# Sch1.net
KiCad netlist of a schematic drawn in Altium Designer
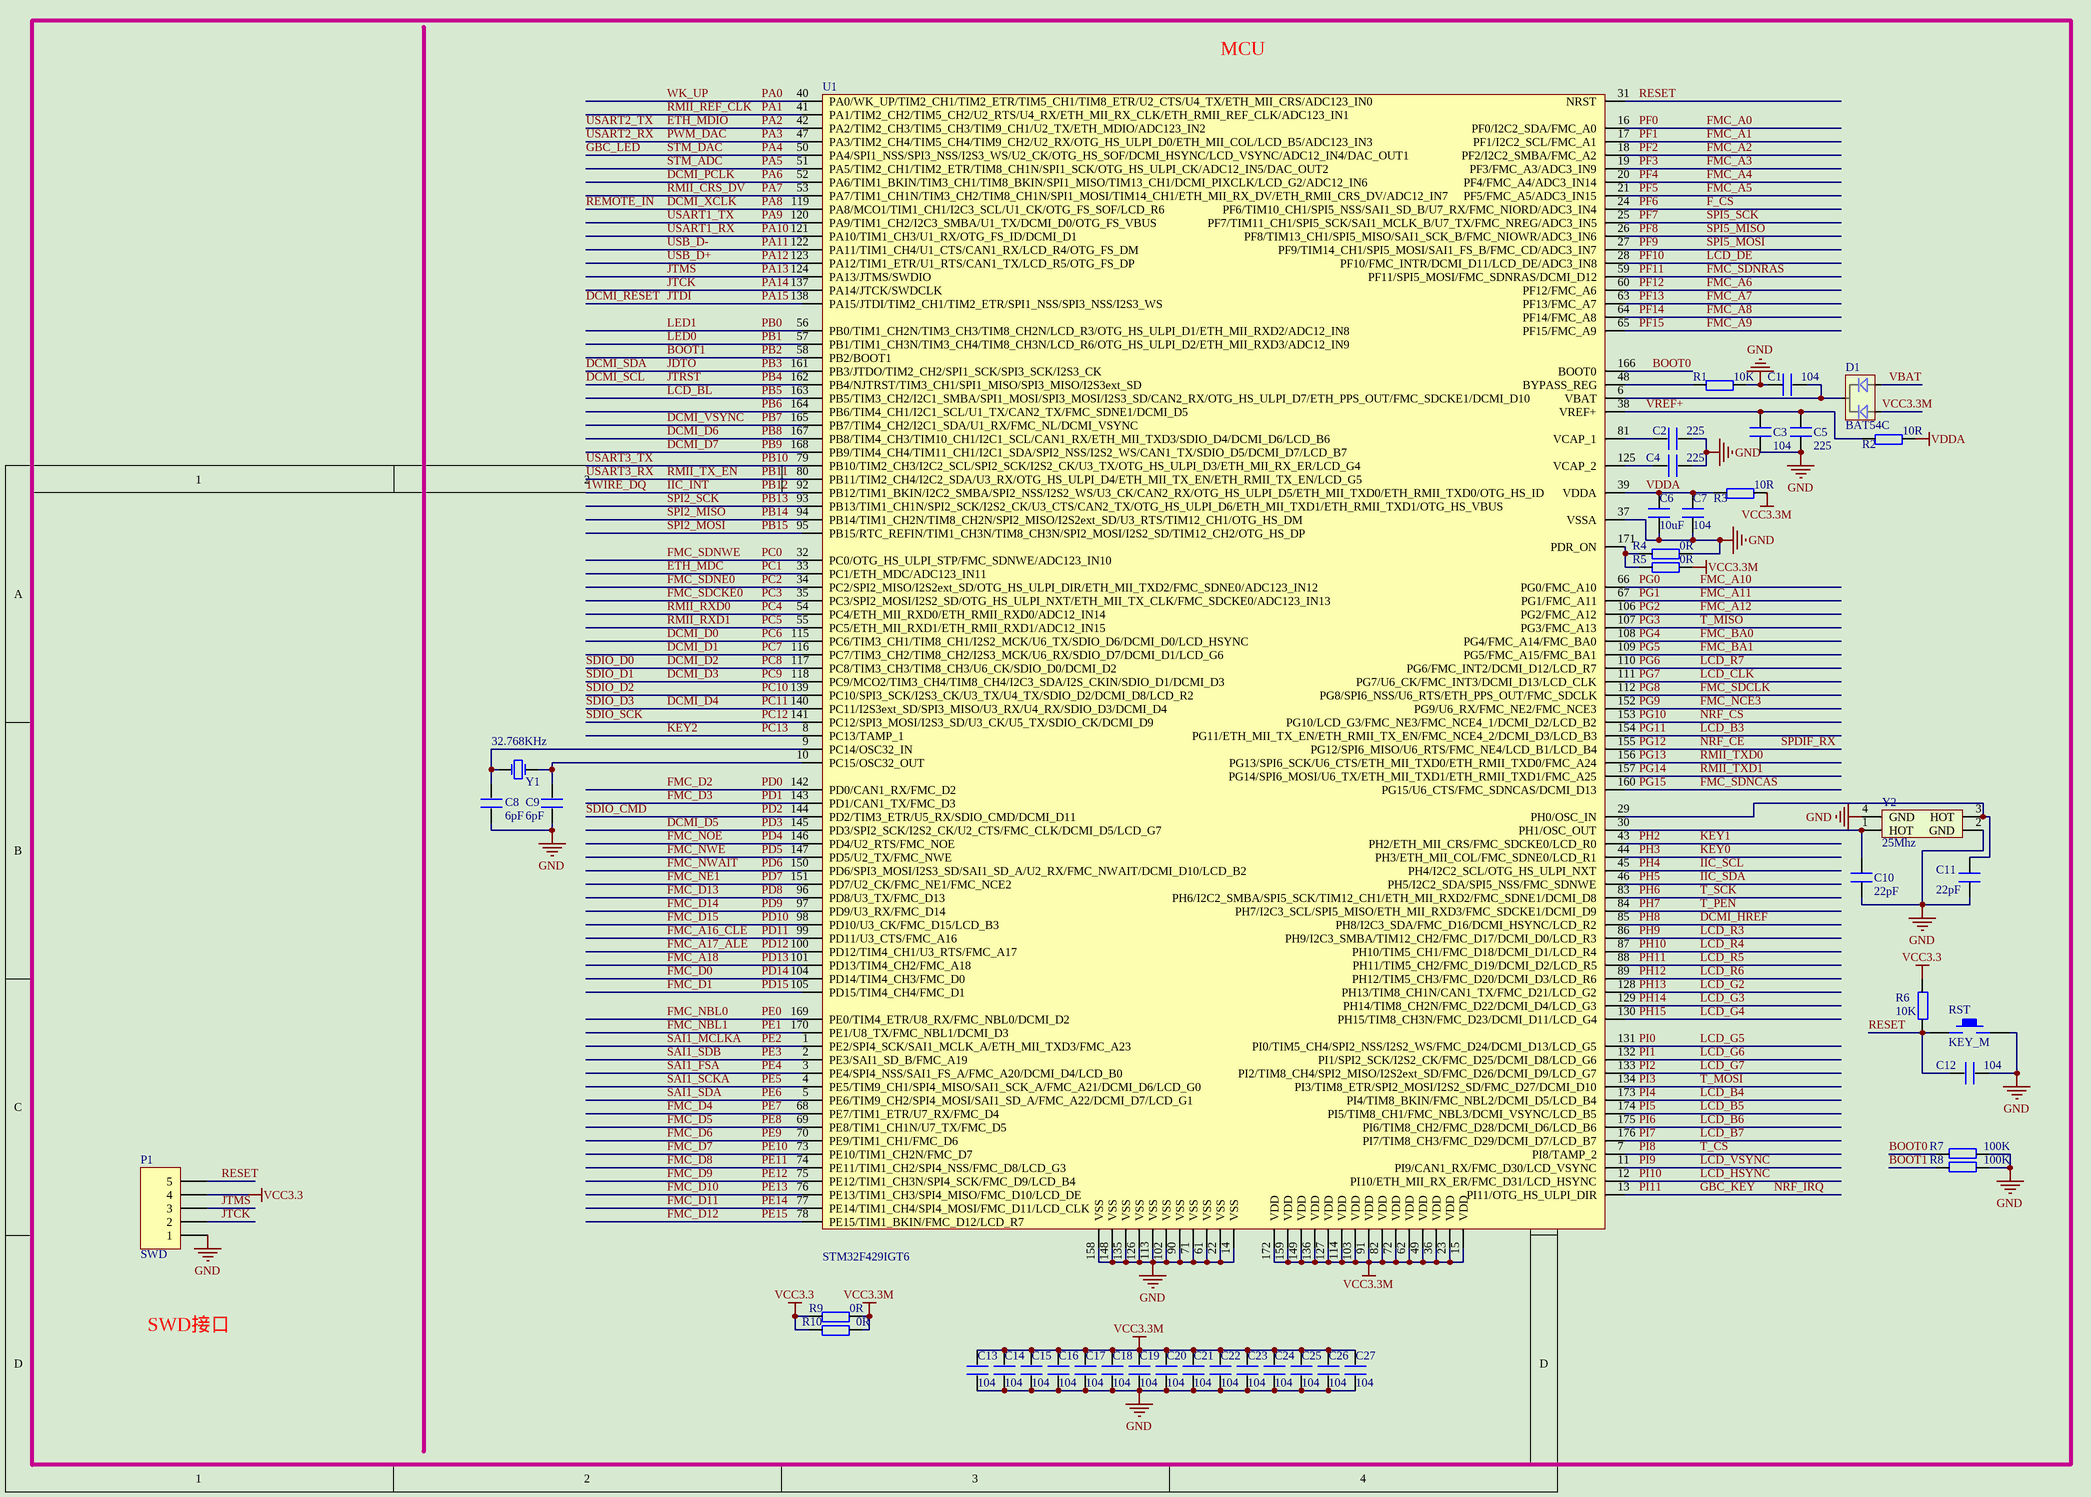
[diagram p0: Sch1.SchDoc]

(export (version "E")
  (design (tool "Eeschema 10.0.6"))
  (components
    (comp (ref "C1") (value "104") (footprint "0402") (libsource (lib "STM32F429_CORE") (part "C")))
    (comp (ref "C2") (value "225") (footprint "0402") (libsource (lib "STM32F429_CORE") (part "C")))
    (comp (ref "C3") (value "104") (footprint "0402") (libsource (lib "STM32F429_CORE") (part "C")))
    (comp (ref "C4") (value "225") (footprint "0402") (libsource (lib "STM32F429_CORE") (part "C")))
    (comp (ref "C5") (value "225") (footprint "0402") (libsource (lib "STM32F429_CORE") (part "C")))
    (comp (ref "C6") (value "10uF") (footprint "0603P") (libsource (lib "STM32F429_CORE") (part "C")))
    (comp (ref "C7") (value "104") (footprint "0402") (libsource (lib "STM32F429_CORE") (part "C")))
    (comp (ref "C8") (value "6pF") (footprint "0402") (libsource (lib "STM32F429_CORE") (part "C")))
    (comp (ref "C9") (value "6pF") (footprint "0402") (libsource (lib "STM32F429_CORE") (part "C")))
    (comp (ref "C10") (value "22pF") (footprint "0402") (libsource (lib "STM32F429_CORE") (part "C")))
    (comp (ref "C11") (value "22pF") (footprint "0402") (libsource (lib "STM32F429_CORE") (part "C")))
    (comp (ref "C12") (value "104") (footprint "0402") (libsource (lib "STM32F429_CORE") (part "C")))
    (comp (ref "C13") (value "104") (footprint "0402") (libsource (lib "STM32F429_CORE") (part "C")))
    (comp (ref "C14") (value "104") (footprint "0402") (libsource (lib "STM32F429_CORE") (part "C")))
    (comp (ref "C15") (value "104") (footprint "0402") (libsource (lib "STM32F429_CORE") (part "C")))
    (comp (ref "C16") (value "104") (footprint "0402") (libsource (lib "STM32F429_CORE") (part "C")))
    (comp (ref "C17") (value "104") (footprint "0402") (libsource (lib "STM32F429_CORE") (part "C")))
    (comp (ref "C18") (value "104") (footprint "0402") (libsource (lib "STM32F429_CORE") (part "C")))
    (comp (ref "C19") (value "104") (footprint "0402") (libsource (lib "STM32F429_CORE") (part "C")))
    (comp (ref "C20") (value "104") (footprint "0402") (libsource (lib "STM32F429_CORE") (part "C")))
    (comp (ref "C21") (value "104") (footprint "0402") (libsource (lib "STM32F429_CORE") (part "C")))
    (comp (ref "C22") (value "104") (footprint "0402") (libsource (lib "STM32F429_CORE") (part "C")))
    (comp (ref "C23") (value "104") (footprint "0402") (libsource (lib "STM32F429_CORE") (part "C")))
    (comp (ref "C24") (value "104") (footprint "0402") (libsource (lib "STM32F429_CORE") (part "C")))
    (comp (ref "C25") (value "104") (footprint "0402") (libsource (lib "STM32F429_CORE") (part "C")))
    (comp (ref "C26") (value "104") (footprint "0402") (libsource (lib "STM32F429_CORE") (part "C")))
    (comp (ref "C27") (value "104") (footprint "0402") (libsource (lib "STM32F429_CORE") (part "C")))
    (comp (ref "D1")
      (value "BAT54C")
      (footprint "SOT-23")
      (description "双肖特基二极管")
      (libsource (lib "STM32F429_CORE") (part "BAT54C"))
    )
    (comp (ref "P1")
      (value "SWD")
      (footprint "HDR1X5")
      (description "Header, 5-Pin")
      (fields (field (name "PUBLISHER") "Altium Limited"))
      (libsource (lib "STM32F429_CORE") (part "Header 5"))
    )
    (comp (ref "R1") (value "10K") (footprint "0402") (libsource (lib "STM32F429_CORE") (part "R")))
    (comp (ref "R2") (value "10R") (footprint "0402") (libsource (lib "STM32F429_CORE") (part "R")))
    (comp (ref "R3") (value "10R") (footprint "0402") (libsource (lib "STM32F429_CORE") (part "R")))
    (comp (ref "R4") (value "0R") (footprint "0402") (libsource (lib "STM32F429_CORE") (part "R")))
    (comp (ref "R5") (value "0R") (footprint "0402") (libsource (lib "STM32F429_CORE") (part "R")))
    (comp (ref "R6") (value "10K") (footprint "0402") (libsource (lib "STM32F429_CORE") (part "R")))
    (comp (ref "R7") (value "100K") (footprint "0402") (libsource (lib "STM32F429_CORE") (part "R")))
    (comp (ref "R8") (value "100K") (footprint "0402") (libsource (lib "STM32F429_CORE") (part "R")))
    (comp (ref "R9") (value "0R") (footprint "0402") (libsource (lib "STM32F429_CORE") (part "R")))
    (comp (ref "R10") (value "0R") (footprint "0402") (libsource (lib "STM32F429_CORE") (part "R")))
    (comp (ref "RST")
      (value "KEY_M")
      (footprint "KEY_SOP3625")
      (libsource (lib "STM32F429_CORE") (part "KEY_M"))
    )
    (comp (ref "U1")
      (value "STM32F429IGT6")
      (footprint "LQFP176")
      (libsource (lib "STM32F429_CORE") (part "STM32F429IGT6"))
    )
    (comp (ref "Y1")
      (value "32.768KHz")
      (footprint "XTAL3215")
      (description "普通晶振")
      (fields (field (name "PUBLISHER") "Altium Limited"))
      (libsource (lib "STM32F429_CORE") (part "XTAL"))
    )
    (comp (ref "Y2")
      (value "25Mhz")
      (footprint "XTAL3225")
      (description "3225贴片无源晶振")
      (libsource (lib "STM32F429_CORE") (part "XTAL_3225"))
    )
  )
  (nets
    (net (code "1") (name "/1WIRE_DQ") (class "Default")
      (node (ref "U1") (pin "92") (pinfunction "PB12/TIM1_BKIN/I2C2_SMBA/SPI2_NSS/I2S2_WS/U3_CK/CAN2_RX/OTG_HS_ULPI_D5/ETH_MII_TXD0/ETH_RMII_TXD0/OTG_HS_ID_92") (pintype "passive"))
    )
    (net (code "2") (name "/BOOT0") (class "Default")
      (node (ref "R7") (pin "2") (pintype "passive"))
      (node (ref "U1") (pin "166") (pinfunction "BOOT0_166") (pintype "passive"))
    )
    (net (code "3") (name "/BOOT1") (class "Default")
      (node (ref "R8") (pin "2") (pintype "passive"))
      (node (ref "U1") (pin "58") (pinfunction "PB2/BOOT1_58") (pintype "passive"))
    )
    (net (code "4") (name "/DCMI_D0") (class "Default")
      (node (ref "U1") (pin "115") (pinfunction "PC6/TIM3_CH1/TIM8_CH1/I2S2_MCK/U6_TX/SDIO_D6/DCMI_D0/LCD_HSYNC_115") (pintype "passive"))
    )
    (net (code "5") (name "/DCMI_D1") (class "Default")
      (node (ref "U1") (pin "116") (pinfunction "PC7/TIM3_CH2/TIM8_CH2/I2S3_MCK/U6_RX/SDIO_D7/DCMI_D1/LCD_G6_116") (pintype "passive"))
    )
    (net (code "6") (name "/DCMI_D2") (class "Default")
      (node (ref "U1") (pin "117") (pinfunction "PC8/TIM3_CH3/TIM8_CH3/U6_CK/SDIO_D0/DCMI_D2_117") (pintype "passive"))
    )
    (net (code "7") (name "/DCMI_D3") (class "Default")
      (node (ref "U1") (pin "118") (pinfunction "PC9/MCO2/TIM3_CH4/TIM8_CH4/I2C3_SDA/I2S_CKIN/SDIO_D1/DCMI_D3_118") (pintype "passive"))
    )
    (net (code "8") (name "/DCMI_D4") (class "Default")
      (node (ref "U1") (pin "140") (pinfunction "PC11/I2S3ext_SD/SPI3_MISO/U3_RX/U4_RX/SDIO_D3/DCMI_D4_140") (pintype "passive"))
    )
    (net (code "9") (name "/DCMI_D5") (class "Default")
      (node (ref "U1") (pin "145") (pinfunction "PD3/SPI2_SCK/I2S2_CK/U2_CTS/FMC_CLK/DCMI_D5/LCD_G7_145") (pintype "passive"))
    )
    (net (code "10") (name "/DCMI_D6") (class "Default")
      (node (ref "U1") (pin "167") (pinfunction "PB8/TIM4_CH3/TIM10_CH1/I2C1_SCL/CAN1_RX/ETH_MII_TXD3/SDIO_D4/DCMI_D6/LCD_B6_167") (pintype "passive"))
    )
    (net (code "11") (name "/DCMI_D7") (class "Default")
      (node (ref "U1") (pin "168") (pinfunction "PB9/TIM4_CH4/TIM11_CH1/I2C1_SDA/SPI2_NSS/I2S2_WS/CAN1_TX/SDIO_D5/DCMI_D7/LCD_B7_168") (pintype "passive"))
    )
    (net (code "12") (name "/DCMI_HREF") (class "Default")
      (node (ref "U1") (pin "85") (pinfunction "PH8/I2C3_SDA/FMC_D16/DCMI_HSYNC/LCD_R2_85") (pintype "passive"))
    )
    (net (code "13") (name "/DCMI_PCLK") (class "Default")
      (node (ref "U1") (pin "52") (pinfunction "PA6/TIM1_BKIN/TIM3_CH1/TIM8_BKIN/SPI1_MISO/TIM13_CH1/DCMI_PIXCLK/LCD_G2/ADC12_IN6_52") (pintype "passive"))
    )
    (net (code "14") (name "/DCMI_RESET") (class "Default")
      (node (ref "U1") (pin "138") (pinfunction "PA15/JTDI/TIM2_CH1/TIM2_ETR/SPI1_NSS/SPI3_NSS/I2S3_WS_138") (pintype "passive"))
    )
    (net (code "15") (name "/DCMI_SCL") (class "Default")
      (node (ref "U1") (pin "162") (pinfunction "PB4/NJTRST/TIM3_CH1/SPI1_MISO/SPI3_MISO/I2S3ext_SD_162") (pintype "passive"))
    )
    (net (code "16") (name "/DCMI_SDA") (class "Default")
      (node (ref "U1") (pin "161") (pinfunction "PB3/JTDO/TIM2_CH2/SPI1_SCK/SPI3_SCK/I2S3_CK_161") (pintype "passive"))
    )
    (net (code "17") (name "/DCMI_VSYNC") (class "Default")
      (node (ref "U1") (pin "165") (pinfunction "PB7/TIM4_CH2/I2C1_SDA/U1_RX/FMC_NL/DCMI_VSYNC_165") (pintype "passive"))
    )
    (net (code "18") (name "/DCMI_XCLK") (class "Default")
      (node (ref "U1") (pin "119") (pinfunction "PA8/MCO1/TIM1_CH1/I2C3_SCL/U1_CK/OTG_FS_SOF/LCD_R6_119") (pintype "passive"))
    )
    (net (code "19") (name "/ETH_MDC") (class "Default")
      (node (ref "U1") (pin "33") (pinfunction "PC1/ETH_MDC/ADC123_IN11_33") (pintype "passive"))
    )
    (net (code "20") (name "/ETH_MDIO") (class "Default")
      (node (ref "U1") (pin "42") (pinfunction "PA2/TIM2_CH3/TIM5_CH3/TIM9_CH1/U2_TX/ETH_MDIO/ADC123_IN2_42") (pintype "passive"))
    )
    (net (code "21") (name "/FMC_A0") (class "Default")
      (node (ref "U1") (pin "16") (pinfunction "PF0/I2C2_SDA/FMC_A0_16") (pintype "passive"))
    )
    (net (code "22") (name "/FMC_A1") (class "Default")
      (node (ref "U1") (pin "17") (pinfunction "PF1/I2C2_SCL/FMC_A1_17") (pintype "passive"))
    )
    (net (code "23") (name "/FMC_A2") (class "Default")
      (node (ref "U1") (pin "18") (pinfunction "PF2/I2C2_SMBA/FMC_A2_18") (pintype "passive"))
    )
    (net (code "24") (name "/FMC_A3") (class "Default")
      (node (ref "U1") (pin "19") (pinfunction "PF3/FMC_A3/ADC3_IN9_19") (pintype "passive"))
    )
    (net (code "25") (name "/FMC_A4") (class "Default")
      (node (ref "U1") (pin "20") (pinfunction "PF4/FMC_A4/ADC3_IN14_20") (pintype "passive"))
    )
    (net (code "26") (name "/FMC_A5") (class "Default")
      (node (ref "U1") (pin "21") (pinfunction "PF5/FMC_A5/ADC3_IN15_21") (pintype "passive"))
    )
    (net (code "27") (name "/FMC_A6") (class "Default")
      (node (ref "U1") (pin "60") (pinfunction "PF12/FMC_A6_60") (pintype "passive"))
    )
    (net (code "28") (name "/FMC_A7") (class "Default")
      (node (ref "U1") (pin "63") (pinfunction "PF13/FMC_A7_63") (pintype "passive"))
    )
    (net (code "29") (name "/FMC_A8") (class "Default")
      (node (ref "U1") (pin "64") (pinfunction "PF14/FMC_A8_64") (pintype "passive"))
    )
    (net (code "30") (name "/FMC_A9") (class "Default")
      (node (ref "U1") (pin "65") (pinfunction "PF15/FMC_A9_65") (pintype "passive"))
    )
    (net (code "31") (name "/FMC_A10") (class "Default")
      (node (ref "U1") (pin "66") (pinfunction "PG0/FMC_A10_66") (pintype "passive"))
    )
    (net (code "32") (name "/FMC_A11") (class "Default")
      (node (ref "U1") (pin "67") (pinfunction "PG1/FMC_A11_67") (pintype "passive"))
    )
    (net (code "33") (name "/FMC_A12") (class "Default")
      (node (ref "U1") (pin "106") (pinfunction "PG2/FMC_A12_106") (pintype "passive"))
    )
    (net (code "34") (name "/FMC_A16_CLE") (class "Default")
      (node (ref "U1") (pin "99") (pinfunction "PD11/U3_CTS/FMC_A16_99") (pintype "passive"))
    )
    (net (code "35") (name "/FMC_A17_ALE") (class "Default")
      (node (ref "U1") (pin "100") (pinfunction "PD12/TIM4_CH1/U3_RTS/FMC_A17_100") (pintype "passive"))
    )
    (net (code "36") (name "/FMC_A18") (class "Default")
      (node (ref "U1") (pin "101") (pinfunction "PD13/TIM4_CH2/FMC_A18_101") (pintype "passive"))
    )
    (net (code "37") (name "/FMC_BA0") (class "Default")
      (node (ref "U1") (pin "108") (pinfunction "PG4/FMC_A14/FMC_BA0_108") (pintype "passive"))
    )
    (net (code "38") (name "/FMC_BA1") (class "Default")
      (node (ref "U1") (pin "109") (pinfunction "PG5/FMC_A15/FMC_BA1_109") (pintype "passive"))
    )
    (net (code "39") (name "/FMC_D0") (class "Default")
      (node (ref "U1") (pin "104") (pinfunction "PD14/TIM4_CH3/FMC_D0_104") (pintype "passive"))
    )
    (net (code "40") (name "/FMC_D1") (class "Default")
      (node (ref "U1") (pin "105") (pinfunction "PD15/TIM4_CH4/FMC_D1_105") (pintype "passive"))
    )
    (net (code "41") (name "/FMC_D2") (class "Default")
      (node (ref "U1") (pin "142") (pinfunction "PD0/CAN1_RX/FMC_D2_142") (pintype "passive"))
    )
    (net (code "42") (name "/FMC_D3") (class "Default")
      (node (ref "U1") (pin "143") (pinfunction "PD1/CAN1_TX/FMC_D3_143") (pintype "passive"))
    )
    (net (code "43") (name "/FMC_D4") (class "Default")
      (node (ref "U1") (pin "68") (pinfunction "PE7/TIM1_ETR/U7_RX/FMC_D4_68") (pintype "passive"))
    )
    (net (code "44") (name "/FMC_D5") (class "Default")
      (node (ref "U1") (pin "69") (pinfunction "PE8/TIM1_CH1N/U7_TX/FMC_D5_69") (pintype "passive"))
    )
    (net (code "45") (name "/FMC_D6") (class "Default")
      (node (ref "U1") (pin "70") (pinfunction "PE9/TIM1_CH1/FMC_D6_70") (pintype "passive"))
    )
    (net (code "46") (name "/FMC_D7") (class "Default")
      (node (ref "U1") (pin "73") (pinfunction "PE10/TIM1_CH2N/FMC_D7_73") (pintype "passive"))
    )
    (net (code "47") (name "/FMC_D8") (class "Default")
      (node (ref "U1") (pin "74") (pinfunction "PE11/TIM1_CH2/SPI4_NSS/FMC_D8/LCD_G3_74") (pintype "passive"))
    )
    (net (code "48") (name "/FMC_D9") (class "Default")
      (node (ref "U1") (pin "75") (pinfunction "PE12/TIM1_CH3N/SPI4_SCK/FMC_D9/LCD_B4_75") (pintype "passive"))
    )
    (net (code "49") (name "/FMC_D10") (class "Default")
      (node (ref "U1") (pin "76") (pinfunction "PE13/TIM1_CH3/SPI4_MISO/FMC_D10/LCD_DE_76") (pintype "passive"))
    )
    (net (code "50") (name "/FMC_D11") (class "Default")
      (node (ref "U1") (pin "77") (pinfunction "PE14/TIM1_CH4/SPI4_MOSI/FMC_D11/LCD_CLK_77") (pintype "passive"))
    )
    (net (code "51") (name "/FMC_D12") (class "Default")
      (node (ref "U1") (pin "78") (pinfunction "PE15/TIM1_BKIN/FMC_D12/LCD_R7_78") (pintype "passive"))
    )
    (net (code "52") (name "/FMC_D13") (class "Default")
      (node (ref "U1") (pin "96") (pinfunction "PD8/U3_TX/FMC_D13_96") (pintype "passive"))
    )
    (net (code "53") (name "/FMC_D14") (class "Default")
      (node (ref "U1") (pin "97") (pinfunction "PD9/U3_RX/FMC_D14_97") (pintype "passive"))
    )
    (net (code "54") (name "/FMC_D15") (class "Default")
      (node (ref "U1") (pin "98") (pinfunction "PD10/U3_CK/FMC_D15/LCD_B3_98") (pintype "passive"))
    )
    (net (code "55") (name "/FMC_NBL0") (class "Default")
      (node (ref "U1") (pin "169") (pinfunction "PE0/TIM4_ETR/U8_RX/FMC_NBL0/DCMI_D2_169") (pintype "passive"))
    )
    (net (code "56") (name "/FMC_NBL1") (class "Default")
      (node (ref "U1") (pin "170") (pinfunction "PE1/U8_TX/FMC_NBL1/DCMI_D3_170") (pintype "passive"))
    )
    (net (code "57") (name "/FMC_NCE3") (class "Default")
      (node (ref "U1") (pin "152") (pinfunction "PG9/U6_RX/FMC_NE2/FMC_NCE3_152") (pintype "passive"))
    )
    (net (code "58") (name "/FMC_NE1") (class "Default")
      (node (ref "U1") (pin "151") (pinfunction "PD7/U2_CK/FMC_NE1/FMC_NCE2_151") (pintype "passive"))
    )
    (net (code "59") (name "/FMC_NOE") (class "Default")
      (node (ref "U1") (pin "146") (pinfunction "PD4/U2_RTS/FMC_NOE_146") (pintype "passive"))
    )
    (net (code "60") (name "/FMC_NWAIT") (class "Default")
      (node (ref "U1") (pin "150") (pinfunction "PD6/SPI3_MOSI/I2S3_SD/SAI1_SD_A/U2_RX/FMC_NWAIT/DCMI_D10/LCD_B2_150") (pintype "passive"))
    )
    (net (code "61") (name "/FMC_NWE") (class "Default")
      (node (ref "U1") (pin "147") (pinfunction "PD5/U2_TX/FMC_NWE_147") (pintype "passive"))
    )
    (net (code "62") (name "/FMC_SDCKE0") (class "Default")
      (node (ref "U1") (pin "35") (pinfunction "PC3/SPI2_MOSI/I2S2_SD/OTG_HS_ULPI_NXT/ETH_MII_TX_CLK/FMC_SDCKE0/ADC123_IN13_35") (pintype "passive"))
    )
    (net (code "63") (name "/FMC_SDCLK") (class "Default")
      (node (ref "U1") (pin "112") (pinfunction "PG8/SPI6_NSS/U6_RTS/ETH_PPS_OUT/FMC_SDCLK_112") (pintype "passive"))
    )
    (net (code "64") (name "/FMC_SDNCAS") (class "Default")
      (node (ref "U1") (pin "160") (pinfunction "PG15/U6_CTS/FMC_SDNCAS/DCMI_D13_160") (pintype "passive"))
    )
    (net (code "65") (name "/FMC_SDNE0") (class "Default")
      (node (ref "U1") (pin "34") (pinfunction "PC2/SPI2_MISO/I2S2ext_SD/OTG_HS_ULPI_DIR/ETH_MII_TXD2/FMC_SDNE0/ADC123_IN12_34") (pintype "passive"))
    )
    (net (code "66") (name "/FMC_SDNRAS") (class "Default")
      (node (ref "U1") (pin "59") (pinfunction "PF11/SPI5_MOSI/FMC_SDNRAS/DCMI_D12_59") (pintype "passive"))
    )
    (net (code "67") (name "/FMC_SDNWE") (class "Default")
      (node (ref "U1") (pin "32") (pinfunction "PC0/OTG_HS_ULPI_STP/FMC_SDNWE/ADC123_IN10_32") (pintype "passive"))
    )
    (net (code "68") (name "/F_CS") (class "Default")
      (node (ref "U1") (pin "24") (pinfunction "PF6/TIM10_CH1/SPI5_NSS/SAI1_SD_B/U7_RX/FMC_NIORD/ADC3_IN4_24") (pintype "passive"))
    )
    (net (code "69") (name "/GBC_KEY") (class "Default")
      (node (ref "U1") (pin "13") (pinfunction "PI11/OTG_HS_ULPI_DIR_13") (pintype "passive"))
    )
    (net (code "70") (name "/GBC_LED") (class "Default")
      (node (ref "U1") (pin "50") (pinfunction "PA4/SPI1_NSS/SPI3_NSS/I2S3_WS/U2_CK/OTG_HS_SOF/DCMI_HSYNC/LCD_VSYNC/ADC12_IN4/DAC_OUT1_50") (pintype "passive"))
    )
    (net (code "71") (name "/IIC_SCL") (class "Default")
      (node (ref "U1") (pin "45") (pinfunction "PH4/I2C2_SCL/OTG_HS_ULPI_NXT_45") (pintype "passive"))
    )
    (net (code "72") (name "/IIC_SDA") (class "Default")
      (node (ref "U1") (pin "46") (pinfunction "PH5/I2C2_SDA/SPI5_NSS/FMC_SDNWE_46") (pintype "passive"))
    )
    (net (code "73") (name "/JTCK") (class "Default")
      (node (ref "P1") (pin "2") (pinfunction "2_2") (pintype "passive"))
      (node (ref "U1") (pin "137") (pinfunction "PA14/JTCK/SWDCLK_137") (pintype "passive"))
    )
    (net (code "74") (name "/JTMS") (class "Default")
      (node (ref "P1") (pin "3") (pinfunction "3_3") (pintype "passive"))
      (node (ref "U1") (pin "124") (pinfunction "PA13/JTMS/SWDIO_124") (pintype "passive"))
    )
    (net (code "75") (name "/KEY0") (class "Default")
      (node (ref "U1") (pin "44") (pinfunction "PH3/ETH_MII_COL/FMC_SDNE0/LCD_R1_44") (pintype "passive"))
    )
    (net (code "76") (name "/KEY1") (class "Default")
      (node (ref "U1") (pin "43") (pinfunction "PH2/ETH_MII_CRS/FMC_SDCKE0/LCD_R0_43") (pintype "passive"))
    )
    (net (code "77") (name "/KEY2") (class "Default")
      (node (ref "U1") (pin "8") (pinfunction "PC13/TAMP_1_8") (pintype "passive"))
    )
    (net (code "78") (name "/LCD_B3") (class "Default")
      (node (ref "U1") (pin "154") (pinfunction "PG11/ETH_MII_TX_EN/ETH_RMII_TX_EN/FMC_NCE4_2/DCMI_D3/LCD_B3_154") (pintype "passive"))
    )
    (net (code "79") (name "/LCD_B4") (class "Default")
      (node (ref "U1") (pin "173") (pinfunction "PI4/TIM8_BKIN/FMC_NBL2/DCMI_D5/LCD_B4_173") (pintype "passive"))
    )
    (net (code "80") (name "/LCD_B5") (class "Default")
      (node (ref "U1") (pin "174") (pinfunction "PI5/TIM8_CH1/FMC_NBL3/DCMI_VSYNC/LCD_B5_174") (pintype "passive"))
    )
    (net (code "81") (name "/LCD_B6") (class "Default")
      (node (ref "U1") (pin "175") (pinfunction "PI6/TIM8_CH2/FMC_D28/DCMI_D6/LCD_B6_175") (pintype "passive"))
    )
    (net (code "82") (name "/LCD_B7") (class "Default")
      (node (ref "U1") (pin "176") (pinfunction "PI7/TIM8_CH3/FMC_D29/DCMI_D7/LCD_B7_176") (pintype "passive"))
    )
    (net (code "83") (name "/LCD_BL") (class "Default")
      (node (ref "U1") (pin "163") (pinfunction "PB5/TIM3_CH2/I2C1_SMBA/SPI1_MOSI/SPI3_MOSI/I2S3_SD/CAN2_RX/OTG_HS_ULPI_D7/ETH_PPS_OUT/FMC_SDCKE1/DCMI_D10_163") (pintype "passive"))
    )
    (net (code "84") (name "/LCD_CLK") (class "Default")
      (node (ref "U1") (pin "111") (pinfunction "PG7/U6_CK/FMC_INT3/DCMI_D13/LCD_CLK_111") (pintype "passive"))
    )
    (net (code "85") (name "/LCD_DE") (class "Default")
      (node (ref "U1") (pin "28") (pinfunction "PF10/FMC_INTR/DCMI_D11/LCD_DE/ADC3_IN8_28") (pintype "passive"))
    )
    (net (code "86") (name "/LCD_G2") (class "Default")
      (node (ref "U1") (pin "128") (pinfunction "PH13/TIM8_CH1N/CAN1_TX/FMC_D21/LCD_G2_128") (pintype "passive"))
    )
    (net (code "87") (name "/LCD_G3") (class "Default")
      (node (ref "U1") (pin "129") (pinfunction "PH14/TIM8_CH2N/FMC_D22/DCMI_D4/LCD_G3_129") (pintype "passive"))
    )
    (net (code "88") (name "/LCD_G4") (class "Default")
      (node (ref "U1") (pin "130") (pinfunction "PH15/TIM8_CH3N/FMC_D23/DCMI_D11/LCD_G4_130") (pintype "passive"))
    )
    (net (code "89") (name "/LCD_G5") (class "Default")
      (node (ref "U1") (pin "131") (pinfunction "PI0/TIM5_CH4/SPI2_NSS/I2S2_WS/FMC_D24/DCMI_D13/LCD_G5_131") (pintype "passive"))
    )
    (net (code "90") (name "/LCD_G6") (class "Default")
      (node (ref "U1") (pin "132") (pinfunction "PI1/SPI2_SCK/I2S2_CK/FMC_D25/DCMI_D8/LCD_G6_132") (pintype "passive"))
    )
    (net (code "91") (name "/LCD_G7") (class "Default")
      (node (ref "U1") (pin "133") (pinfunction "PI2/TIM8_CH4/SPI2_MISO/I2S2ext_SD/FMC_D26/DCMI_D9/LCD_G7_133") (pintype "passive"))
    )
    (net (code "92") (name "/LCD_HSYNC") (class "Default")
      (node (ref "U1") (pin "12") (pinfunction "PI10/ETH_MII_RX_ER/FMC_D31/LCD_HSYNC_12") (pintype "passive"))
    )
    (net (code "93") (name "/LCD_R3") (class "Default")
      (node (ref "U1") (pin "86") (pinfunction "PH9/I2C3_SMBA/TIM12_CH2/FMC_D17/DCMI_D0/LCD_R3_86") (pintype "passive"))
    )
    (net (code "94") (name "/LCD_R4") (class "Default")
      (node (ref "U1") (pin "87") (pinfunction "PH10/TIM5_CH1/FMC_D18/DCMI_D1/LCD_R4_87") (pintype "passive"))
    )
    (net (code "95") (name "/LCD_R5") (class "Default")
      (node (ref "U1") (pin "88") (pinfunction "PH11/TIM5_CH2/FMC_D19/DCMI_D2/LCD_R5_88") (pintype "passive"))
    )
    (net (code "96") (name "/LCD_R6") (class "Default")
      (node (ref "U1") (pin "89") (pinfunction "PH12/TIM5_CH3/FMC_D20/DCMI_D3/LCD_R6_89") (pintype "passive"))
    )
    (net (code "97") (name "/LCD_R7") (class "Default")
      (node (ref "U1") (pin "110") (pinfunction "PG6/FMC_INT2/DCMI_D12/LCD_R7_110") (pintype "passive"))
    )
    (net (code "98") (name "/LCD_VSYNC") (class "Default")
      (node (ref "U1") (pin "11") (pinfunction "PI9/CAN1_RX/FMC_D30/LCD_VSYNC_11") (pintype "passive"))
    )
    (net (code "99") (name "/LED0") (class "Default")
      (node (ref "U1") (pin "57") (pinfunction "PB1/TIM1_CH3N/TIM3_CH4/TIM8_CH3N/LCD_R6/OTG_HS_ULPI_D2/ETH_MII_RXD3/ADC12_IN9_57") (pintype "passive"))
    )
    (net (code "100") (name "/LED1") (class "Default")
      (node (ref "U1") (pin "56") (pinfunction "PB0/TIM1_CH2N/TIM3_CH3/TIM8_CH2N/LCD_R3/OTG_HS_ULPI_D1/ETH_MII_RXD2/ADC12_IN8_56") (pintype "passive"))
    )
    (net (code "101") (name "/NRF_CE") (class "Default")
      (node (ref "U1") (pin "155") (pinfunction "PG12/SPI6_MISO/U6_RTS/FMC_NE4/LCD_B1/LCD_B4_155") (pintype "passive"))
    )
    (net (code "102") (name "/NRF_CS") (class "Default")
      (node (ref "U1") (pin "153") (pinfunction "PG10/LCD_G3/FMC_NE3/FMC_NCE4_1/DCMI_D2/LCD_B2_153") (pintype "passive"))
    )
    (net (code "103") (name "/PA0") (class "Default")
      (node (ref "U1") (pin "40") (pinfunction "PA0/WK_UP/TIM2_CH1/TIM2_ETR/TIM5_CH1/TIM8_ETR/U2_CTS/U4_TX/ETH_MII_CRS/ADC123_IN0_40") (pintype "passive"))
    )
    (net (code "104") (name "/PA1") (class "Default")
      (node (ref "U1") (pin "41") (pinfunction "PA1/TIM2_CH2/TIM5_CH2/U2_RTS/U4_RX/ETH_MII_RX_CLK/ETH_RMII_REF_CLK/ADC123_IN1_41") (pintype "passive"))
    )
    (net (code "105") (name "/PA3") (class "Default")
      (node (ref "U1") (pin "47") (pinfunction "PA3/TIM2_CH4/TIM5_CH4/TIM9_CH2/U2_RX/OTG_HS_ULPI_D0/ETH_MII_COL/LCD_B5/ADC123_IN3_47") (pintype "passive"))
    )
    (net (code "106") (name "/PA5") (class "Default")
      (node (ref "U1") (pin "51") (pinfunction "PA5/TIM2_CH1/TIM2_ETR/TIM8_CH1N/SPI1_SCK/OTG_HS_ULPI_CK/ADC12_IN5/DAC_OUT2_51") (pintype "passive"))
    )
    (net (code "107") (name "/PA7") (class "Default")
      (node (ref "U1") (pin "53") (pinfunction "PA7/TIM1_CH1N/TIM3_CH2/TIM8_CH1N/SPI1_MOSI/TIM14_CH1/ETH_MII_RX_DV/ETH_RMII_CRS_DV/ADC12_IN7_53") (pintype "passive"))
    )
    (net (code "108") (name "/PA9") (class "Default")
      (node (ref "U1") (pin "120") (pinfunction "PA9/TIM1_CH2/I2C3_SMBA/U1_TX/DCMI_D0/OTG_FS_VBUS_120") (pintype "passive"))
    )
    (net (code "109") (name "/PA10") (class "Default")
      (node (ref "U1") (pin "121") (pinfunction "PA10/TIM1_CH3/U1_RX/OTG_FS_ID/DCMI_D1_121") (pintype "passive"))
    )
    (net (code "110") (name "/PA11") (class "Default")
      (node (ref "U1") (pin "122") (pinfunction "PA11/TIM1_CH4/U1_CTS/CAN1_RX/LCD_R4/OTG_FS_DM_122") (pintype "passive"))
    )
    (net (code "111") (name "/PA12") (class "Default")
      (node (ref "U1") (pin "123") (pinfunction "PA12/TIM1_ETR/U1_RTS/CAN1_TX/LCD_R5/OTG_FS_DP_123") (pintype "passive"))
    )
    (net (code "112") (name "/PB6") (class "Default")
      (node (ref "U1") (pin "164") (pinfunction "PB6/TIM4_CH1/I2C1_SCL/U1_TX/CAN2_TX/FMC_SDNE1/DCMI_D5_164") (pintype "passive"))
    )
    (net (code "113") (name "/PB10") (class "Default")
      (node (ref "U1") (pin "79") (pinfunction "PB10/TIM2_CH3/I2C2_SCL/SPI2_SCK/I2S2_CK/U3_TX/OTG_HS_ULPI_D3/ETH_MII_RX_ER/LCD_G4_79") (pintype "passive"))
    )
    (net (code "114") (name "/PB11") (class "Default")
      (node (ref "U1") (pin "80") (pinfunction "PB11/TIM2_CH4/I2C2_SDA/U3_RX/OTG_HS_ULPI_D4/ETH_MII_TX_EN/ETH_RMII_TX_EN/LCD_G5_80") (pintype "passive"))
    )
    (net (code "115") (name "/PB13") (class "Default")
      (node (ref "U1") (pin "93") (pinfunction "PB13/TIM1_CH1N/SPI2_SCK/I2S2_CK/U3_CTS/CAN2_TX/OTG_HS_ULPI_D6/ETH_MII_TXD1/ETH_RMII_TXD1/OTG_HS_VBUS_93") (pintype "passive"))
    )
    (net (code "116") (name "/PB14") (class "Default")
      (node (ref "U1") (pin "94") (pinfunction "PB14/TIM1_CH2N/TIM8_CH2N/SPI2_MISO/I2S2ext_SD/U3_RTS/TIM12_CH1/OTG_HS_DM_94") (pintype "passive"))
    )
    (net (code "117") (name "/PB15") (class "Default")
      (node (ref "U1") (pin "95") (pinfunction "PB15/RTC_REFIN/TIM1_CH3N/TIM8_CH3N/SPI2_MOSI/I2S2_SD/TIM12_CH2/OTG_HS_DP_95") (pintype "passive"))
    )
    (net (code "118") (name "/PC4") (class "Default")
      (node (ref "U1") (pin "54") (pinfunction "PC4/ETH_MII_RXD0/ETH_RMII_RXD0/ADC12_IN14_54") (pintype "passive"))
    )
    (net (code "119") (name "/PC5") (class "Default")
      (node (ref "U1") (pin "55") (pinfunction "PC5/ETH_MII_RXD1/ETH_RMII_RXD1/ADC12_IN15_55") (pintype "passive"))
    )
    (net (code "120") (name "/PC10") (class "Default")
      (node (ref "U1") (pin "139") (pinfunction "PC10/SPI3_SCK/I2S3_CK/U3_TX/U4_TX/SDIO_D2/DCMI_D8/LCD_R2_139") (pintype "passive"))
    )
    (net (code "121") (name "/PC12") (class "Default")
      (node (ref "U1") (pin "141") (pinfunction "PC12/SPI3_MOSI/I2S3_SD/U3_CK/U5_TX/SDIO_CK/DCMI_D9_141") (pintype "passive"))
    )
    (net (code "122") (name "/PD2") (class "Default")
      (node (ref "U1") (pin "144") (pinfunction "PD2/TIM3_ETR/U5_RX/SDIO_CMD/DCMI_D11_144") (pintype "passive"))
    )
    (net (code "123") (name "/PE2") (class "Default")
      (node (ref "U1") (pin "1") (pinfunction "PE2/SPI4_SCK/SAI1_MCLK_A/ETH_MII_TXD3/FMC_A23_1") (pintype "passive"))
    )
    (net (code "124") (name "/PE3") (class "Default")
      (node (ref "U1") (pin "2") (pinfunction "PE3/SAI1_SD_B/FMC_A19_2") (pintype "passive"))
    )
    (net (code "125") (name "/PE4") (class "Default")
      (node (ref "U1") (pin "3") (pinfunction "PE4/SPI4_NSS/SAI1_FS_A/FMC_A20/DCMI_D4/LCD_B0_3") (pintype "passive"))
    )
    (net (code "126") (name "/PE5") (class "Default")
      (node (ref "U1") (pin "4") (pinfunction "PE5/TIM9_CH1/SPI4_MISO/SAI1_SCK_A/FMC_A21/DCMI_D6/LCD_G0_4") (pintype "passive"))
    )
    (net (code "127") (name "/PE6") (class "Default")
      (node (ref "U1") (pin "5") (pinfunction "PE6/TIM9_CH2/SPI4_MOSI/SAI1_SD_A/FMC_A22/DCMI_D7/LCD_G1_5") (pintype "passive"))
    )
    (net (code "128") (name "/PF7") (class "Default")
      (node (ref "U1") (pin "25") (pinfunction "PF7/TIM11_CH1/SPI5_SCK/SAI1_MCLK_B/U7_TX/FMC_NREG/ADC3_IN5_25") (pintype "passive"))
    )
    (net (code "129") (name "/PF8") (class "Default")
      (node (ref "U1") (pin "26") (pinfunction "PF8/TIM13_CH1/SPI5_MISO/SAI1_SCK_B/FMC_NIOWR/ADC3_IN6_26") (pintype "passive"))
    )
    (net (code "130") (name "/PF9") (class "Default")
      (node (ref "U1") (pin "27") (pinfunction "PF9/TIM14_CH1/SPI5_MOSI/SAI1_FS_B/FMC_CD/ADC3_IN7_27") (pintype "passive"))
    )
    (net (code "131") (name "/PG3") (class "Default")
      (node (ref "U1") (pin "107") (pinfunction "PG3/FMC_A13_107") (pintype "passive"))
    )
    (net (code "132") (name "/PG13") (class "Default")
      (node (ref "U1") (pin "156") (pinfunction "PG13/SPI6_SCK/U6_CTS/ETH_MII_TXD0/ETH_RMII_TXD0/FMC_A24_156") (pintype "passive"))
    )
    (net (code "133") (name "/PG14") (class "Default")
      (node (ref "U1") (pin "157") (pinfunction "PG14/SPI6_MOSI/U6_TX/ETH_MII_TXD1/ETH_RMII_TXD1/FMC_A25_157") (pintype "passive"))
    )
    (net (code "134") (name "/PH6") (class "Default")
      (node (ref "U1") (pin "83") (pinfunction "PH6/I2C2_SMBA/SPI5_SCK/TIM12_CH1/ETH_MII_RXD2/FMC_SDNE1/DCMI_D8_83") (pintype "passive"))
    )
    (net (code "135") (name "/PH7") (class "Default")
      (node (ref "U1") (pin "84") (pinfunction "PH7/I2C3_SCL/SPI5_MISO/ETH_MII_RXD3/FMC_SDCKE1/DCMI_D9_84") (pintype "passive"))
    )
    (net (code "136") (name "/PI3") (class "Default")
      (node (ref "U1") (pin "134") (pinfunction "PI3/TIM8_ETR/SPI2_MOSI/I2S2_SD/FMC_D27/DCMI_D10_134") (pintype "passive"))
    )
    (net (code "137") (name "/PI8") (class "Default")
      (node (ref "U1") (pin "7") (pinfunction "PI8/TAMP_2_7") (pintype "passive"))
    )
    (net (code "138") (name "/RESET") (class "Default")
      (node (ref "C12") (pin "1") (pintype "passive"))
      (node (ref "P1") (pin "5") (pinfunction "5_5") (pintype "passive"))
      (node (ref "R6") (pin "1") (pintype "passive"))
      (node (ref "RST") (pin "1") (pinfunction "1_1") (pintype "passive"))
      (node (ref "U1") (pin "31") (pinfunction "NRST_31") (pintype "passive"))
    )
    (net (code "139") (name "/VBAT") (class "Default") (node (ref "D1") (pin "2") (pintype "passive")))
    (net (code "140") (name "/VREF+") (class "Default")
      (node (ref "C3") (pin "2") (pintype "passive"))
      (node (ref "C5") (pin "2") (pintype "passive"))
      (node (ref "R2") (pin "1") (pintype "passive"))
      (node (ref "U1") (pin "38") (pinfunction "VREF+_38") (pintype "passive"))
    )
    (net (code "141") (name "GND") (class "Default")
      (node (ref "C1") (pin "1") (pintype "passive"))
      (node (ref "C10") (pin "1") (pintype "passive"))
      (node (ref "C11") (pin "1") (pintype "passive"))
      (node (ref "C12") (pin "2") (pintype "passive"))
      (node (ref "C13") (pin "1") (pintype "passive"))
      (node (ref "C14") (pin "1") (pintype "passive"))
      (node (ref "C15") (pin "1") (pintype "passive"))
      (node (ref "C16") (pin "1") (pintype "passive"))
      (node (ref "C17") (pin "1") (pintype "passive"))
      (node (ref "C18") (pin "1") (pintype "passive"))
      (node (ref "C19") (pin "1") (pintype "passive"))
      (node (ref "C2") (pin "2") (pintype "passive"))
      (node (ref "C20") (pin "1") (pintype "passive"))
      (node (ref "C21") (pin "1") (pintype "passive"))
      (node (ref "C22") (pin "1") (pintype "passive"))
      (node (ref "C23") (pin "1") (pintype "passive"))
      (node (ref "C24") (pin "1") (pintype "passive"))
      (node (ref "C25") (pin "1") (pintype "passive"))
      (node (ref "C26") (pin "1") (pintype "passive"))
      (node (ref "C27") (pin "1") (pintype "passive"))
      (node (ref "C3") (pin "1") (pintype "passive"))
      (node (ref "C4") (pin "1") (pintype "passive"))
      (node (ref "C5") (pin "1") (pintype "passive"))
      (node (ref "C6") (pin "1") (pintype "passive"))
      (node (ref "C7") (pin "1") (pintype "passive"))
      (node (ref "C8") (pin "1") (pintype "passive"))
      (node (ref "C9") (pin "1") (pintype "passive"))
      (node (ref "P1") (pin "1") (pinfunction "1_1") (pintype "passive"))
      (node (ref "R1") (pin "2") (pintype "passive"))
      (node (ref "R4") (pin "2") (pintype "passive"))
      (node (ref "R7") (pin "1") (pintype "passive"))
      (node (ref "R8") (pin "1") (pintype "passive"))
      (node (ref "RST") (pin "2") (pinfunction "2_2") (pintype "passive"))
      (node (ref "U1") (pin "102") (pinfunction "VSS_102") (pintype "passive"))
      (node (ref "U1") (pin "113") (pinfunction "VSS_113") (pintype "passive"))
      (node (ref "U1") (pin "126") (pinfunction "VSS_126") (pintype "passive"))
      (node (ref "U1") (pin "135") (pinfunction "VSS_135") (pintype "passive"))
      (node (ref "U1") (pin "14") (pinfunction "VSS_14") (pintype "passive"))
      (node (ref "U1") (pin "148") (pinfunction "VSS_148") (pintype "passive"))
      (node (ref "U1") (pin "158") (pinfunction "VSS_158") (pintype "passive"))
      (node (ref "U1") (pin "22") (pinfunction "VSS_22") (pintype "passive"))
      (node (ref "U1") (pin "37") (pinfunction "VSSA_37") (pintype "passive"))
      (node (ref "U1") (pin "61") (pinfunction "VSS_61") (pintype "passive"))
      (node (ref "U1") (pin "71") (pinfunction "VSS_71") (pintype "passive"))
      (node (ref "U1") (pin "90") (pinfunction "VSS_90") (pintype "passive"))
      (node (ref "Y2") (pin "2") (pinfunction "GND_2") (pintype "passive"))
      (node (ref "Y2") (pin "4") (pinfunction "GND_4") (pintype "passive"))
    )
    (net (code "142") (name "Net-(U1-BYPASS_REG)") (class "Default")
      (node (ref "R1") (pin "1") (pintype "passive"))
      (node (ref "U1") (pin "48") (pinfunction "BYPASS_REG_48") (pintype "passive"))
    )
    (net (code "143") (name "Net-(U1-PC14{slash}OSC32_IN)") (class "Default")
      (node (ref "C8") (pin "2") (pintype "passive"))
      (node (ref "U1") (pin "9") (pinfunction "PC14/OSC32_IN_9") (pintype "passive"))
      (node (ref "Y1") (pin "1") (pinfunction "OSC1_1") (pintype "passive"))
    )
    (net (code "144") (name "Net-(U1-PC15{slash}OSC32_OUT)") (class "Default")
      (node (ref "C9") (pin "2") (pintype "passive"))
      (node (ref "U1") (pin "10") (pinfunction "PC15/OSC32_OUT_10") (pintype "passive"))
      (node (ref "Y1") (pin "2") (pinfunction "OSC2_2") (pintype "passive"))
    )
    (net (code "145") (name "Net-(U1-PDR_ON)") (class "Default")
      (node (ref "R4") (pin "1") (pintype "passive"))
      (node (ref "R5") (pin "1") (pintype "passive"))
      (node (ref "U1") (pin "171") (pinfunction "PDR_ON_171") (pintype "passive"))
    )
    (net (code "146") (name "Net-(U1-PH0{slash}OSC_IN)") (class "Default")
      (node (ref "C11") (pin "2") (pintype "passive"))
      (node (ref "U1") (pin "29") (pinfunction "PH0/OSC_IN_29") (pintype "passive"))
      (node (ref "Y2") (pin "3") (pinfunction "HOT_3") (pintype "passive"))
    )
    (net (code "147") (name "Net-(U1-PH1{slash}OSC_OUT)") (class "Default")
      (node (ref "C10") (pin "2") (pintype "passive"))
      (node (ref "U1") (pin "30") (pinfunction "PH1/OSC_OUT_30") (pintype "passive"))
      (node (ref "Y2") (pin "1") (pinfunction "HOT_1") (pintype "passive"))
    )
    (net (code "148") (name "Net-(U1-VBAT)") (class "Default")
      (node (ref "C1") (pin "2") (pintype "passive"))
      (node (ref "D1") (pin "3") (pintype "passive"))
      (node (ref "U1") (pin "6") (pinfunction "VBAT_6") (pintype "passive"))
    )
    (net (code "149") (name "Net-(U1-VCAP_1)") (class "Default")
      (node (ref "C2") (pin "1") (pintype "passive"))
      (node (ref "U1") (pin "81") (pinfunction "VCAP_1_81") (pintype "passive"))
    )
    (net (code "150") (name "Net-(U1-VCAP_2)") (class "Default")
      (node (ref "C4") (pin "2") (pintype "passive"))
      (node (ref "U1") (pin "125") (pinfunction "VCAP_2_125") (pintype "passive"))
    )
    (net (code "151") (name "VCC3.3") (class "Default")
      (node (ref "P1") (pin "4") (pinfunction "4_4") (pintype "passive"))
      (node (ref "R10") (pin "1") (pintype "passive"))
      (node (ref "R6") (pin "2") (pintype "passive"))
      (node (ref "R9") (pin "1") (pintype "passive"))
    )
    (net (code "152") (name "VCC3.3M") (class "Default")
      (node (ref "C13") (pin "2") (pintype "passive"))
      (node (ref "C14") (pin "2") (pintype "passive"))
      (node (ref "C15") (pin "2") (pintype "passive"))
      (node (ref "C16") (pin "2") (pintype "passive"))
      (node (ref "C17") (pin "2") (pintype "passive"))
      (node (ref "C18") (pin "2") (pintype "passive"))
      (node (ref "C19") (pin "2") (pintype "passive"))
      (node (ref "C20") (pin "2") (pintype "passive"))
      (node (ref "C21") (pin "2") (pintype "passive"))
      (node (ref "C22") (pin "2") (pintype "passive"))
      (node (ref "C23") (pin "2") (pintype "passive"))
      (node (ref "C24") (pin "2") (pintype "passive"))
      (node (ref "C25") (pin "2") (pintype "passive"))
      (node (ref "C26") (pin "2") (pintype "passive"))
      (node (ref "C27") (pin "2") (pintype "passive"))
      (node (ref "D1") (pin "1") (pintype "passive"))
      (node (ref "R10") (pin "2") (pintype "passive"))
      (node (ref "R3") (pin "2") (pintype "passive"))
      (node (ref "R5") (pin "2") (pintype "passive"))
      (node (ref "R9") (pin "2") (pintype "passive"))
      (node (ref "U1") (pin "103") (pinfunction "VDD_103") (pintype "passive"))
      (node (ref "U1") (pin "114") (pinfunction "VDD_114") (pintype "passive"))
      (node (ref "U1") (pin "127") (pinfunction "VDD_127") (pintype "passive"))
      (node (ref "U1") (pin "136") (pinfunction "VDD_136") (pintype "passive"))
      (node (ref "U1") (pin "149") (pinfunction "VDD_149") (pintype "passive"))
      (node (ref "U1") (pin "15") (pinfunction "VDD_15") (pintype "passive"))
      (node (ref "U1") (pin "159") (pinfunction "VDD_159") (pintype "passive"))
      (node (ref "U1") (pin "172") (pinfunction "VDD_172") (pintype "passive"))
      (node (ref "U1") (pin "23") (pinfunction "VDD_23") (pintype "passive"))
      (node (ref "U1") (pin "36") (pinfunction "VDD_36") (pintype "passive"))
      (node (ref "U1") (pin "49") (pinfunction "VDD_49") (pintype "passive"))
      (node (ref "U1") (pin "62") (pinfunction "VDD_62") (pintype "passive"))
      (node (ref "U1") (pin "72") (pinfunction "VDD_72") (pintype "passive"))
      (node (ref "U1") (pin "82") (pinfunction "VDD_82") (pintype "passive"))
      (node (ref "U1") (pin "91") (pinfunction "VDD_91") (pintype "passive"))
    )
    (net (code "153") (name "VDDA") (class "Default")
      (node (ref "C6") (pin "2") (pintype "passive"))
      (node (ref "C7") (pin "2") (pintype "passive"))
      (node (ref "R2") (pin "2") (pintype "passive"))
      (node (ref "R3") (pin "1") (pintype "passive"))
      (node (ref "U1") (pin "39") (pinfunction "VDDA_39") (pintype "passive"))
    )
  )
)
